# 6_-_Z7010_DDR_INF.net
KiCad netlist of a schematic drawn in Altium Designer
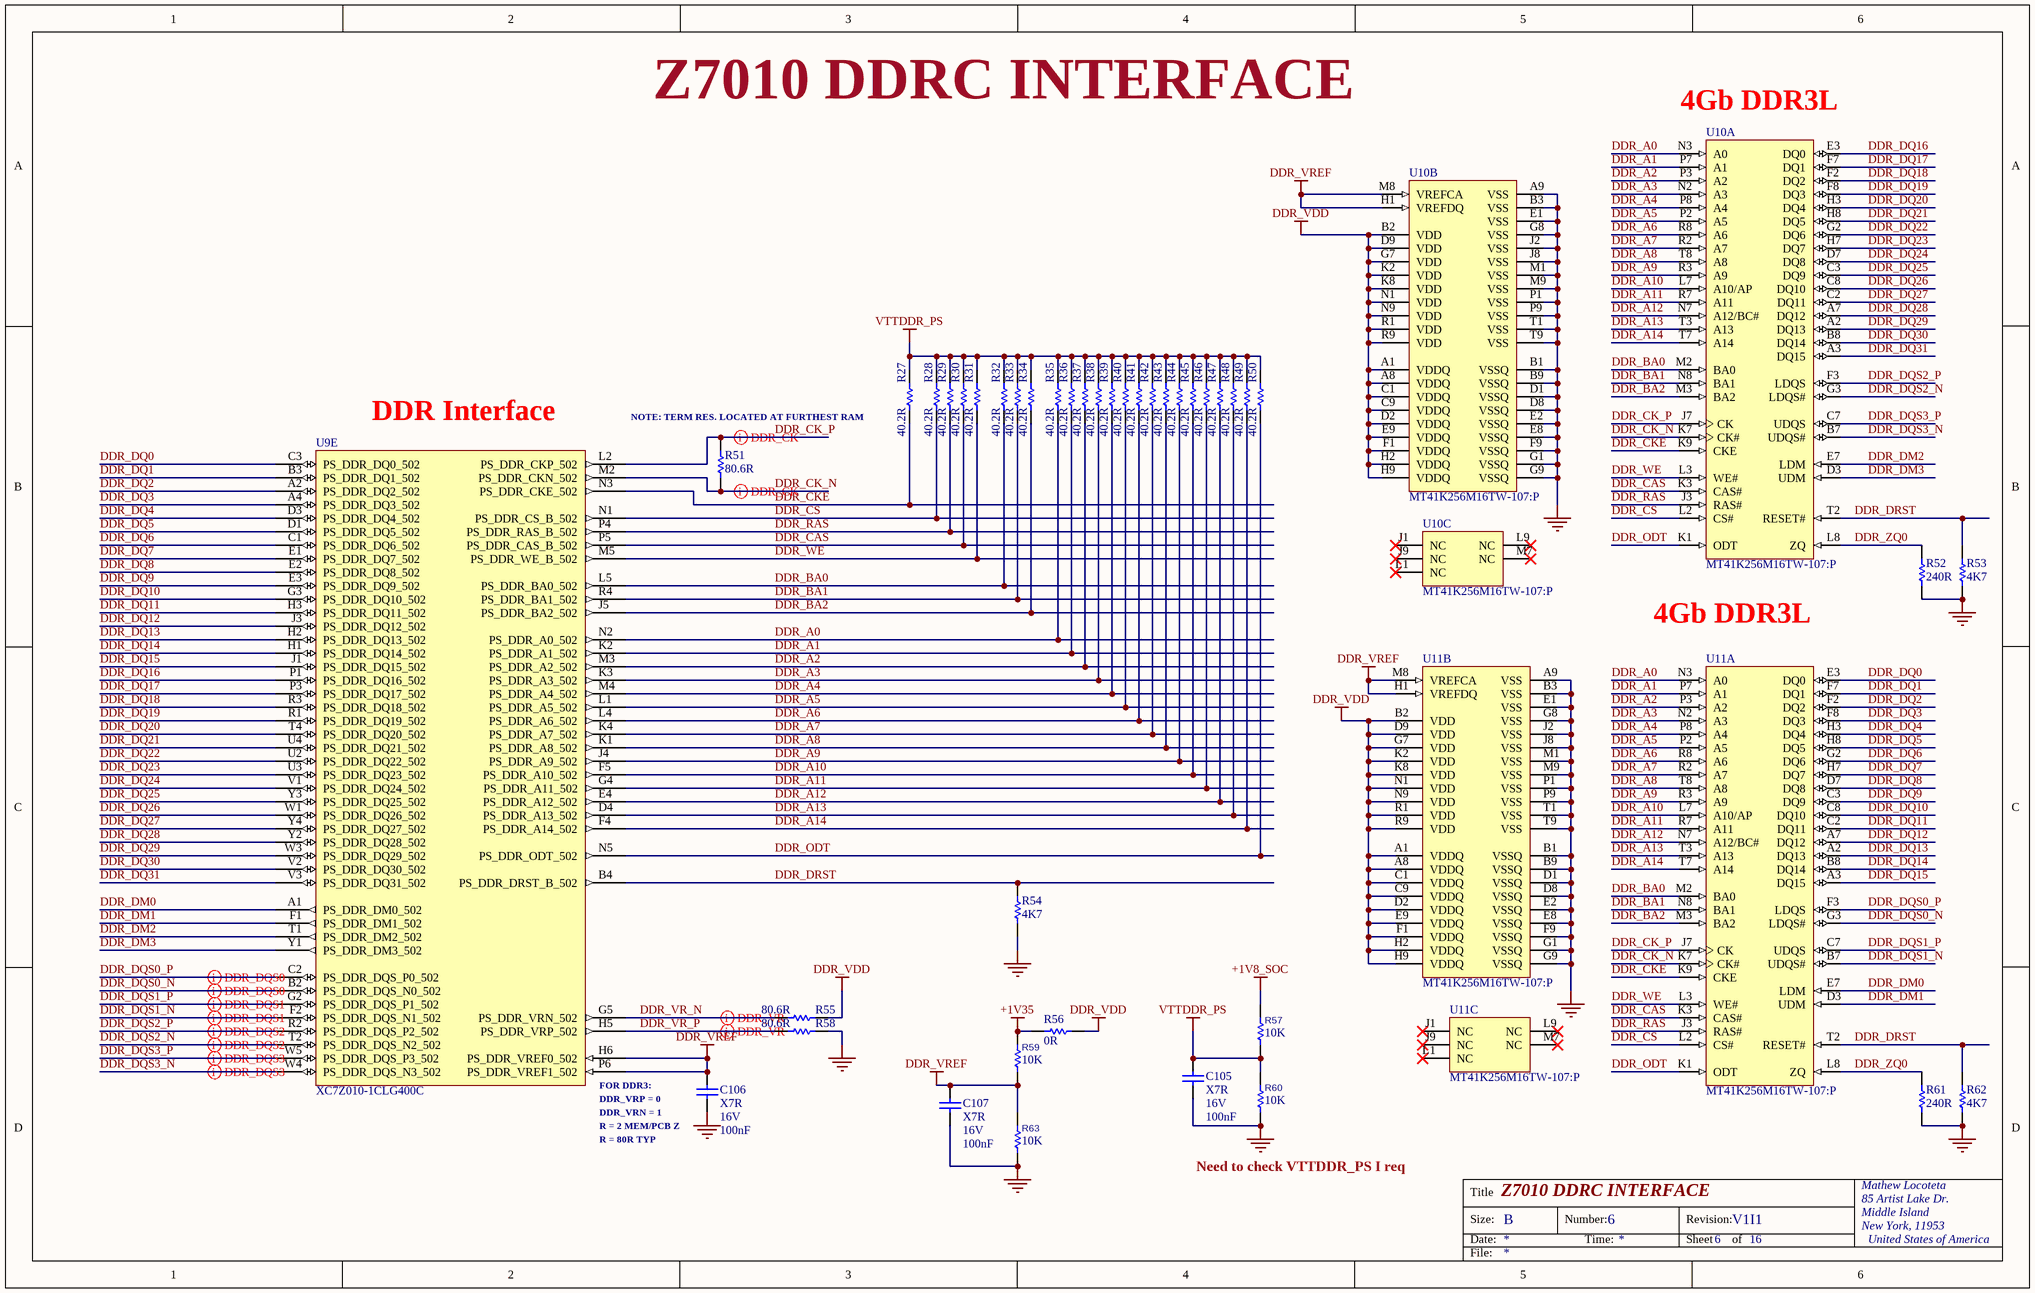
[diagram p0: [6] - Z7010 DDR INF.SchDoc]

(export (version "E")
  (design (tool "Eeschema 10.0.6"))
  (components
    (comp (ref "C105")
      (value "100nF 0402 16V")
      (fields
        (field (name "MANUFACTURER") "KEMET")
        (field (name "MANUFACTURER PART NUMBER") "C0402C104J4RACTU")
        (field (name "TOLERANCE") "5%")
        (field (name "DIELECTRIC") "X7R")
        (field (name "VOLTAGE RATING") "16V")
        (field (name "CAPACITANCE") "100nF")
      )
      (libsource (lib "Zynq 7000") (part "C0402C104J4RACTU"))
    )
    (comp (ref "C106")
      (value "100nF 0402 16V")
      (fields
        (field (name "MANUFACTURER") "KEMET")
        (field (name "MANUFACTURER PART NUMBER") "C0402C104J4RACTU")
        (field (name "TOLERANCE") "5%")
        (field (name "DIELECTRIC") "X7R")
        (field (name "VOLTAGE RATING") "16V")
        (field (name "CAPACITANCE") "100nF")
      )
      (libsource (lib "Zynq 7000") (part "C0402C104J4RACTU"))
    )
    (comp (ref "C107")
      (value "100nF 0402 16V")
      (fields
        (field (name "MANUFACTURER") "KEMET")
        (field (name "MANUFACTURER PART NUMBER") "C0402C104J4RACTU")
        (field (name "TOLERANCE") "5%")
        (field (name "DIELECTRIC") "X7R")
        (field (name "VOLTAGE RATING") "16V")
        (field (name "CAPACITANCE") "100nF")
      )
      (libsource (lib "Zynq 7000") (part "C0402C104J4RACTU"))
    )
    (comp (ref "R27")
      (value "40R2 1% 0402")
      (description "RES SMD 40.2 OHM 1% 1/16W 0402")
      (fields
        (field (name "MANUFACTURER") "Vishay")
        (field (name "MANUFACTURER PART NUMBER") "CRCW040240R2FKED")
        (field (name "RESISTANCE") "40.2R")
      )
      (libsource (lib "Zynq 7000") (part "CRCW040240R2FKED"))
    )
    (comp (ref "R28")
      (value "40R2 1% 0402")
      (description "RES SMD 40.2 OHM 1% 1/16W 0402")
      (fields
        (field (name "MANUFACTURER") "Vishay")
        (field (name "MANUFACTURER PART NUMBER") "CRCW040240R2FKED")
        (field (name "RESISTANCE") "40.2R")
      )
      (libsource (lib "Zynq 7000") (part "CRCW040240R2FKED"))
    )
    (comp (ref "R29")
      (value "40R2 1% 0402")
      (description "RES SMD 40.2 OHM 1% 1/16W 0402")
      (fields
        (field (name "MANUFACTURER") "Vishay")
        (field (name "MANUFACTURER PART NUMBER") "CRCW040240R2FKED")
        (field (name "RESISTANCE") "40.2R")
      )
      (libsource (lib "Zynq 7000") (part "CRCW040240R2FKED"))
    )
    (comp (ref "R30")
      (value "40R2 1% 0402")
      (description "RES SMD 40.2 OHM 1% 1/16W 0402")
      (fields
        (field (name "MANUFACTURER") "Vishay")
        (field (name "MANUFACTURER PART NUMBER") "CRCW040240R2FKED")
        (field (name "RESISTANCE") "40.2R")
      )
      (libsource (lib "Zynq 7000") (part "CRCW040240R2FKED"))
    )
    (comp (ref "R31")
      (value "40R2 1% 0402")
      (description "RES SMD 40.2 OHM 1% 1/16W 0402")
      (fields
        (field (name "MANUFACTURER") "Vishay")
        (field (name "MANUFACTURER PART NUMBER") "CRCW040240R2FKED")
        (field (name "RESISTANCE") "40.2R")
      )
      (libsource (lib "Zynq 7000") (part "CRCW040240R2FKED"))
    )
    (comp (ref "R32")
      (value "40R2 1% 0402")
      (description "RES SMD 40.2 OHM 1% 1/16W 0402")
      (fields
        (field (name "MANUFACTURER") "Vishay")
        (field (name "MANUFACTURER PART NUMBER") "CRCW040240R2FKED")
        (field (name "RESISTANCE") "40.2R")
      )
      (libsource (lib "Zynq 7000") (part "CRCW040240R2FKED"))
    )
    (comp (ref "R33")
      (value "40R2 1% 0402")
      (description "RES SMD 40.2 OHM 1% 1/16W 0402")
      (fields
        (field (name "MANUFACTURER") "Vishay")
        (field (name "MANUFACTURER PART NUMBER") "CRCW040240R2FKED")
        (field (name "RESISTANCE") "40.2R")
      )
      (libsource (lib "Zynq 7000") (part "CRCW040240R2FKED"))
    )
    (comp (ref "R34")
      (value "40R2 1% 0402")
      (description "RES SMD 40.2 OHM 1% 1/16W 0402")
      (fields
        (field (name "MANUFACTURER") "Vishay")
        (field (name "MANUFACTURER PART NUMBER") "CRCW040240R2FKED")
        (field (name "RESISTANCE") "40.2R")
      )
      (libsource (lib "Zynq 7000") (part "CRCW040240R2FKED"))
    )
    (comp (ref "R35")
      (value "40R2 1% 0402")
      (description "RES SMD 40.2 OHM 1% 1/16W 0402")
      (fields
        (field (name "MANUFACTURER") "Vishay")
        (field (name "MANUFACTURER PART NUMBER") "CRCW040240R2FKED")
        (field (name "RESISTANCE") "40.2R")
      )
      (libsource (lib "Zynq 7000") (part "CRCW040240R2FKED"))
    )
    (comp (ref "R36")
      (value "40R2 1% 0402")
      (description "RES SMD 40.2 OHM 1% 1/16W 0402")
      (fields
        (field (name "MANUFACTURER") "Vishay")
        (field (name "MANUFACTURER PART NUMBER") "CRCW040240R2FKED")
        (field (name "RESISTANCE") "40.2R")
      )
      (libsource (lib "Zynq 7000") (part "CRCW040240R2FKED"))
    )
    (comp (ref "R37")
      (value "40R2 1% 0402")
      (description "RES SMD 40.2 OHM 1% 1/16W 0402")
      (fields
        (field (name "MANUFACTURER") "Vishay")
        (field (name "MANUFACTURER PART NUMBER") "CRCW040240R2FKED")
        (field (name "RESISTANCE") "40.2R")
      )
      (libsource (lib "Zynq 7000") (part "CRCW040240R2FKED"))
    )
    (comp (ref "R38")
      (value "40R2 1% 0402")
      (description "RES SMD 40.2 OHM 1% 1/16W 0402")
      (fields
        (field (name "MANUFACTURER") "Vishay")
        (field (name "MANUFACTURER PART NUMBER") "CRCW040240R2FKED")
        (field (name "RESISTANCE") "40.2R")
      )
      (libsource (lib "Zynq 7000") (part "CRCW040240R2FKED"))
    )
    (comp (ref "R39")
      (value "40R2 1% 0402")
      (description "RES SMD 40.2 OHM 1% 1/16W 0402")
      (fields
        (field (name "MANUFACTURER") "Vishay")
        (field (name "MANUFACTURER PART NUMBER") "CRCW040240R2FKED")
        (field (name "RESISTANCE") "40.2R")
      )
      (libsource (lib "Zynq 7000") (part "CRCW040240R2FKED"))
    )
    (comp (ref "R40")
      (value "40R2 1% 0402")
      (description "RES SMD 40.2 OHM 1% 1/16W 0402")
      (fields
        (field (name "MANUFACTURER") "Vishay")
        (field (name "MANUFACTURER PART NUMBER") "CRCW040240R2FKED")
        (field (name "RESISTANCE") "40.2R")
      )
      (libsource (lib "Zynq 7000") (part "CRCW040240R2FKED"))
    )
    (comp (ref "R41")
      (value "40R2 1% 0402")
      (description "RES SMD 40.2 OHM 1% 1/16W 0402")
      (fields
        (field (name "MANUFACTURER") "Vishay")
        (field (name "MANUFACTURER PART NUMBER") "CRCW040240R2FKED")
        (field (name "RESISTANCE") "40.2R")
      )
      (libsource (lib "Zynq 7000") (part "CRCW040240R2FKED"))
    )
    (comp (ref "R42")
      (value "40R2 1% 0402")
      (description "RES SMD 40.2 OHM 1% 1/16W 0402")
      (fields
        (field (name "MANUFACTURER") "Vishay")
        (field (name "MANUFACTURER PART NUMBER") "CRCW040240R2FKED")
        (field (name "RESISTANCE") "40.2R")
      )
      (libsource (lib "Zynq 7000") (part "CRCW040240R2FKED"))
    )
    (comp (ref "R43")
      (value "40R2 1% 0402")
      (description "RES SMD 40.2 OHM 1% 1/16W 0402")
      (fields
        (field (name "MANUFACTURER") "Vishay")
        (field (name "MANUFACTURER PART NUMBER") "CRCW040240R2FKED")
        (field (name "RESISTANCE") "40.2R")
      )
      (libsource (lib "Zynq 7000") (part "CRCW040240R2FKED"))
    )
    (comp (ref "R44")
      (value "40R2 1% 0402")
      (description "RES SMD 40.2 OHM 1% 1/16W 0402")
      (fields
        (field (name "MANUFACTURER") "Vishay")
        (field (name "MANUFACTURER PART NUMBER") "CRCW040240R2FKED")
        (field (name "RESISTANCE") "40.2R")
      )
      (libsource (lib "Zynq 7000") (part "CRCW040240R2FKED"))
    )
    (comp (ref "R45")
      (value "40R2 1% 0402")
      (description "RES SMD 40.2 OHM 1% 1/16W 0402")
      (fields
        (field (name "MANUFACTURER") "Vishay")
        (field (name "MANUFACTURER PART NUMBER") "CRCW040240R2FKED")
        (field (name "RESISTANCE") "40.2R")
      )
      (libsource (lib "Zynq 7000") (part "CRCW040240R2FKED"))
    )
    (comp (ref "R46")
      (value "40R2 1% 0402")
      (description "RES SMD 40.2 OHM 1% 1/16W 0402")
      (fields
        (field (name "MANUFACTURER") "Vishay")
        (field (name "MANUFACTURER PART NUMBER") "CRCW040240R2FKED")
        (field (name "RESISTANCE") "40.2R")
      )
      (libsource (lib "Zynq 7000") (part "CRCW040240R2FKED"))
    )
    (comp (ref "R47")
      (value "40R2 1% 0402")
      (description "RES SMD 40.2 OHM 1% 1/16W 0402")
      (fields
        (field (name "MANUFACTURER") "Vishay")
        (field (name "MANUFACTURER PART NUMBER") "CRCW040240R2FKED")
        (field (name "RESISTANCE") "40.2R")
      )
      (libsource (lib "Zynq 7000") (part "CRCW040240R2FKED"))
    )
    (comp (ref "R48")
      (value "40R2 1% 0402")
      (description "RES SMD 40.2 OHM 1% 1/16W 0402")
      (fields
        (field (name "MANUFACTURER") "Vishay")
        (field (name "MANUFACTURER PART NUMBER") "CRCW040240R2FKED")
        (field (name "RESISTANCE") "40.2R")
      )
      (libsource (lib "Zynq 7000") (part "CRCW040240R2FKED"))
    )
    (comp (ref "R49")
      (value "40R2 1% 0402")
      (description "RES SMD 40.2 OHM 1% 1/16W 0402")
      (fields
        (field (name "MANUFACTURER") "Vishay")
        (field (name "MANUFACTURER PART NUMBER") "CRCW040240R2FKED")
        (field (name "RESISTANCE") "40.2R")
      )
      (libsource (lib "Zynq 7000") (part "CRCW040240R2FKED"))
    )
    (comp (ref "R50")
      (value "40R2 1% 0402")
      (description "RES SMD 40.2 OHM 1% 1/16W 0402")
      (fields
        (field (name "MANUFACTURER") "Vishay")
        (field (name "MANUFACTURER PART NUMBER") "CRCW040240R2FKED")
        (field (name "RESISTANCE") "40.2R")
      )
      (libsource (lib "Zynq 7000") (part "CRCW040240R2FKED"))
    )
    (comp (ref "R51")
      (value "80.6R 0402 1%")
      (fields
        (field (name "MANUFACTURER") "Vishay")
        (field (name "MANUFACTURER PART NUMBER") "CRCW040280R6FKED")
        (field (name "TOLERANCE") "1%")
        (field (name "RESISTANCE") "80.6R")
      )
      (libsource (lib "Zynq 7000") (part "CRCW040280R6FKED"))
    )
    (comp (ref "R52")
      (value "240R 0402 1%")
      (description "RES SMD 240 OHM 1% 1/16W 0402")
      (fields
        (field (name "MANUFACTURER") "Vishay")
        (field (name "MANUFACTURER PART NUMBER") "CRCW0402240RFKED")
        (field (name "RESISTANCE") "240R")
      )
      (libsource (lib "Zynq 7000") (part "CRCW0402240RFKED"))
    )
    (comp (ref "R53")
      (value "4K7 0402 1%")
      (description "Resistor SMD 4.7 kOhm 0402 PU=10000 ST, CRCW04024K70FKED, Vishay")
      (fields
        (field (name "MANUFACTURER") "Vishay")
        (field (name "MANUFACTURER PART NUMBER") "CRCW04024K70FKED")
        (field (name "RESISTANCE") "4K7")
      )
      (libsource (lib "Zynq 7000") (part "CRCW04024K70FKED"))
    )
    (comp (ref "R54")
      (value "4K7 0402 1%")
      (description "Resistor SMD 4.7 kOhm 0402 PU=10000 ST, CRCW04024K70FKED, Vishay")
      (fields
        (field (name "MANUFACTURER") "Vishay")
        (field (name "MANUFACTURER PART NUMBER") "CRCW04024K70FKED")
        (field (name "RESISTANCE") "4K7")
      )
      (libsource (lib "Zynq 7000") (part "CRCW04024K70FKED"))
    )
    (comp (ref "R55")
      (value "80.6R 0402 1%")
      (fields
        (field (name "MANUFACTURER") "Vishay")
        (field (name "MANUFACTURER PART NUMBER") "CRCW040280R6FKED")
        (field (name "TOLERANCE") "1%")
        (field (name "RESISTANCE") "80.6R")
      )
      (libsource (lib "Zynq 7000") (part "CRCW040280R6FKED"))
    )
    (comp (ref "R56")
      (value "0R")
      (footprint "r0805")
      (fields
        (field (name "MANUFACTURER") "Stackpole Electronics")
        (field (name "MANUFACTURER PART NUMBER") "RMCF0805ZT0R00")
      )
      (libsource (lib "DVXC4+ ECU (2)") (part "RMCF0805ZT0R00"))
    )
    (comp (ref "R57")
      (value "10K")
      (footprint "R0402")
      (description "RES 10K OHM 1% 1/16W 0402")
      (fields
        (field (name "MANUFACTURER") "Stackpole Electronics")
        (field (name "MANUFACTURER PART NUMBER") "RMCF0402FT10K0")
      )
      (libsource (lib "DVXC4+ ECU (2)") (part "RMCF0402FT10K0"))
    )
    (comp (ref "R58")
      (value "80.6R 0402 1%")
      (fields
        (field (name "MANUFACTURER") "Vishay")
        (field (name "MANUFACTURER PART NUMBER") "CRCW040280R6FKED")
        (field (name "TOLERANCE") "1%")
        (field (name "RESISTANCE") "80.6R")
      )
      (libsource (lib "Zynq 7000") (part "CRCW040280R6FKED"))
    )
    (comp (ref "R59")
      (value "10K")
      (footprint "R0402")
      (description "RES 10K OHM 1% 1/16W 0402")
      (fields
        (field (name "MANUFACTURER") "Stackpole Electronics")
        (field (name "MANUFACTURER PART NUMBER") "RMCF0402FT10K0")
      )
      (libsource (lib "DVXC4+ ECU (2)") (part "RMCF0402FT10K0"))
    )
    (comp (ref "R60")
      (value "10K")
      (footprint "R0402")
      (description "RES 10K OHM 1% 1/16W 0402")
      (fields
        (field (name "MANUFACTURER") "Stackpole Electronics")
        (field (name "MANUFACTURER PART NUMBER") "RMCF0402FT10K0")
      )
      (libsource (lib "DVXC4+ ECU (2)") (part "RMCF0402FT10K0"))
    )
    (comp (ref "R61")
      (value "240R 0402 1%")
      (description "RES SMD 240 OHM 1% 1/16W 0402")
      (fields
        (field (name "MANUFACTURER") "Vishay")
        (field (name "MANUFACTURER PART NUMBER") "CRCW0402240RFKED")
        (field (name "RESISTANCE") "240R")
      )
      (libsource (lib "Zynq 7000") (part "CRCW0402240RFKED"))
    )
    (comp (ref "R62")
      (value "4K7 0402 1%")
      (description "Resistor SMD 4.7 kOhm 0402 PU=10000 ST, CRCW04024K70FKED, Vishay")
      (fields
        (field (name "MANUFACTURER") "Vishay")
        (field (name "MANUFACTURER PART NUMBER") "CRCW04024K70FKED")
        (field (name "RESISTANCE") "4K7")
      )
      (libsource (lib "Zynq 7000") (part "CRCW04024K70FKED"))
    )
    (comp (ref "R63")
      (value "10K")
      (footprint "R0402")
      (description "RES 10K OHM 1% 1/16W 0402")
      (fields
        (field (name "MANUFACTURER") "Stackpole Electronics")
        (field (name "MANUFACTURER PART NUMBER") "RMCF0402FT10K0")
      )
      (libsource (lib "DVXC4+ ECU (2)") (part "RMCF0402FT10K0"))
    )
    (comp (ref "U9")
      (value "XC7Z010-1CLG400C")
      (footprint "CLG400")
      (fields (field (name "GENERIC PART NUMBER") "XC7Z010"))
      (libsource (lib "Altium Content Vault") (part "XNLX-XC7Z010-CLG400"))
    )
    (comp (ref "U10")
      (value "MT41K256M16TW-107:P")
      (footprint "MICT-TW-96")
      (description "DDR3L SDRAM, 4 GB, 933 MHz, 1.283 to 1.45 V, 0 to 95 degC, 96-Pin FBGA, RoHS, Tray")
      (fields (field (name "MANUFACTURER") "Micron"))
      (libsource (lib "Altium Content Vault") (part "MICT-MT41K256M16-TW-96"))
    )
    (comp (ref "U11")
      (value "MT41K256M16TW-107:P")
      (footprint "MICT-TW-96")
      (description "DDR3L SDRAM, 4 GB, 933 MHz, 1.283 to 1.45 V, 0 to 95 degC, 96-Pin FBGA, RoHS, Tray")
      (fields (field (name "MANUFACTURER") "Micron"))
      (libsource (lib "Altium Content Vault") (part "MICT-MT41K256M16-TW-96"))
    )
  )
  (nets
    (net (code "1") (name "+1V8_SOC") (class "Default")
      (node (ref "R57") (pin "2") (pinfunction "2_2") (pintype "passive"))
    )
    (net (code "2") (name "+1V35") (class "Default")
      (node (ref "R56") (pin "2") (pinfunction "2_2") (pintype "passive"))
      (node (ref "R59") (pin "2") (pinfunction "2_2") (pintype "passive"))
    )
    (net (code "3") (name "/DDR_A0") (class "Default")
      (node (ref "R35") (pin "1") (pinfunction "1_1") (pintype "passive"))
      (node (ref "U10") (pin "N3") (pinfunction "A0_N3") (pintype "input"))
      (node (ref "U11") (pin "N3") (pinfunction "A0_N3") (pintype "input"))
      (node (ref "U9") (pin "N2") (pinfunction "PS_DDR_A0_502_N2") (pintype "output"))
    )
    (net (code "4") (name "/DDR_A1") (class "Default")
      (node (ref "R36") (pin "1") (pinfunction "1_1") (pintype "passive"))
      (node (ref "U10") (pin "P7") (pinfunction "A1_P7") (pintype "input"))
      (node (ref "U11") (pin "P7") (pinfunction "A1_P7") (pintype "input"))
      (node (ref "U9") (pin "K2") (pinfunction "PS_DDR_A1_502_K2") (pintype "output"))
    )
    (net (code "5") (name "/DDR_A2") (class "Default")
      (node (ref "R37") (pin "1") (pinfunction "1_1") (pintype "passive"))
      (node (ref "U10") (pin "P3") (pinfunction "A2_P3") (pintype "input"))
      (node (ref "U11") (pin "P3") (pinfunction "A2_P3") (pintype "input"))
      (node (ref "U9") (pin "M3") (pinfunction "PS_DDR_A2_502_M3") (pintype "output"))
    )
    (net (code "6") (name "/DDR_A3") (class "Default")
      (node (ref "R38") (pin "1") (pinfunction "1_1") (pintype "passive"))
      (node (ref "U10") (pin "N2") (pinfunction "A3_N2") (pintype "input"))
      (node (ref "U11") (pin "N2") (pinfunction "A3_N2") (pintype "input"))
      (node (ref "U9") (pin "K3") (pinfunction "PS_DDR_A3_502_K3") (pintype "output"))
    )
    (net (code "7") (name "/DDR_A4") (class "Default")
      (node (ref "R39") (pin "1") (pinfunction "1_1") (pintype "passive"))
      (node (ref "U10") (pin "P8") (pinfunction "A4_P8") (pintype "input"))
      (node (ref "U11") (pin "P8") (pinfunction "A4_P8") (pintype "input"))
      (node (ref "U9") (pin "M4") (pinfunction "PS_DDR_A4_502_M4") (pintype "output"))
    )
    (net (code "8") (name "/DDR_A5") (class "Default")
      (node (ref "R40") (pin "1") (pinfunction "1_1") (pintype "passive"))
      (node (ref "U10") (pin "P2") (pinfunction "A5_P2") (pintype "input"))
      (node (ref "U11") (pin "P2") (pinfunction "A5_P2") (pintype "input"))
      (node (ref "U9") (pin "L1") (pinfunction "PS_DDR_A5_502_L1") (pintype "output"))
    )
    (net (code "9") (name "/DDR_A6") (class "Default")
      (node (ref "R41") (pin "1") (pinfunction "1_1") (pintype "passive"))
      (node (ref "U10") (pin "R8") (pinfunction "A6_R8") (pintype "input"))
      (node (ref "U11") (pin "R8") (pinfunction "A6_R8") (pintype "input"))
      (node (ref "U9") (pin "L4") (pinfunction "PS_DDR_A6_502_L4") (pintype "output"))
    )
    (net (code "10") (name "/DDR_A7") (class "Default")
      (node (ref "R42") (pin "1") (pinfunction "1_1") (pintype "passive"))
      (node (ref "U10") (pin "R2") (pinfunction "A7_R2") (pintype "input"))
      (node (ref "U11") (pin "R2") (pinfunction "A7_R2") (pintype "input"))
      (node (ref "U9") (pin "K4") (pinfunction "PS_DDR_A7_502_K4") (pintype "output"))
    )
    (net (code "11") (name "/DDR_A8") (class "Default")
      (node (ref "R43") (pin "1") (pinfunction "1_1") (pintype "passive"))
      (node (ref "U10") (pin "T8") (pinfunction "A8_T8") (pintype "input"))
      (node (ref "U11") (pin "T8") (pinfunction "A8_T8") (pintype "input"))
      (node (ref "U9") (pin "K1") (pinfunction "PS_DDR_A8_502_K1") (pintype "output"))
    )
    (net (code "12") (name "/DDR_A9") (class "Default")
      (node (ref "R44") (pin "1") (pinfunction "1_1") (pintype "passive"))
      (node (ref "U10") (pin "R3") (pinfunction "A9_R3") (pintype "input"))
      (node (ref "U11") (pin "R3") (pinfunction "A9_R3") (pintype "input"))
      (node (ref "U9") (pin "J4") (pinfunction "PS_DDR_A9_502_J4") (pintype "output"))
    )
    (net (code "13") (name "/DDR_A10") (class "Default")
      (node (ref "R45") (pin "1") (pinfunction "1_1") (pintype "passive"))
      (node (ref "U10") (pin "L7") (pinfunction "A10/AP_L7") (pintype "input"))
      (node (ref "U11") (pin "L7") (pinfunction "A10/AP_L7") (pintype "input"))
      (node (ref "U9") (pin "F5") (pinfunction "PS_DDR_A10_502_F5") (pintype "output"))
    )
    (net (code "14") (name "/DDR_A11") (class "Default")
      (node (ref "R46") (pin "1") (pinfunction "1_1") (pintype "passive"))
      (node (ref "U10") (pin "R7") (pinfunction "A11_R7") (pintype "input"))
      (node (ref "U11") (pin "R7") (pinfunction "A11_R7") (pintype "input"))
      (node (ref "U9") (pin "G4") (pinfunction "PS_DDR_A11_502_G4") (pintype "output"))
    )
    (net (code "15") (name "/DDR_A12") (class "Default")
      (node (ref "R47") (pin "1") (pinfunction "1_1") (pintype "passive"))
      (node (ref "U10") (pin "N7") (pinfunction "A12/BC#_N7") (pintype "input"))
      (node (ref "U11") (pin "N7") (pinfunction "A12/BC#_N7") (pintype "input"))
      (node (ref "U9") (pin "E4") (pinfunction "PS_DDR_A12_502_E4") (pintype "output"))
    )
    (net (code "16") (name "/DDR_A13") (class "Default")
      (node (ref "R48") (pin "1") (pinfunction "1_1") (pintype "passive"))
      (node (ref "U10") (pin "T3") (pinfunction "A13_T3") (pintype "input"))
      (node (ref "U11") (pin "T3") (pinfunction "A13_T3") (pintype "input"))
      (node (ref "U9") (pin "D4") (pinfunction "PS_DDR_A13_502_D4") (pintype "output"))
    )
    (net (code "17") (name "/DDR_A14") (class "Default")
      (node (ref "R49") (pin "1") (pinfunction "1_1") (pintype "passive"))
      (node (ref "U10") (pin "T7") (pinfunction "A14_T7") (pintype "input"))
      (node (ref "U11") (pin "T7") (pinfunction "A14_T7") (pintype "input"))
      (node (ref "U9") (pin "F4") (pinfunction "PS_DDR_A14_502_F4") (pintype "output"))
    )
    (net (code "18") (name "/DDR_BA0") (class "Default")
      (node (ref "R32") (pin "1") (pinfunction "1_1") (pintype "passive"))
      (node (ref "U10") (pin "M2") (pinfunction "BA0_M2") (pintype "input"))
      (node (ref "U11") (pin "M2") (pinfunction "BA0_M2") (pintype "input"))
      (node (ref "U9") (pin "L5") (pinfunction "PS_DDR_BA0_502_L5") (pintype "output"))
    )
    (net (code "19") (name "/DDR_BA1") (class "Default")
      (node (ref "R33") (pin "1") (pinfunction "1_1") (pintype "passive"))
      (node (ref "U10") (pin "N8") (pinfunction "BA1_N8") (pintype "input"))
      (node (ref "U11") (pin "N8") (pinfunction "BA1_N8") (pintype "input"))
      (node (ref "U9") (pin "R4") (pinfunction "PS_DDR_BA1_502_R4") (pintype "output"))
    )
    (net (code "20") (name "/DDR_BA2") (class "Default")
      (node (ref "R34") (pin "1") (pinfunction "1_1") (pintype "passive"))
      (node (ref "U10") (pin "M3") (pinfunction "BA2_M3") (pintype "input"))
      (node (ref "U11") (pin "M3") (pinfunction "BA2_M3") (pintype "input"))
      (node (ref "U9") (pin "J5") (pinfunction "PS_DDR_BA2_502_J5") (pintype "output"))
    )
    (net (code "21") (name "/DDR_CAS") (class "Default")
      (node (ref "R30") (pin "1") (pinfunction "1_1") (pintype "passive"))
      (node (ref "U10") (pin "K3") (pinfunction "CAS#_K3") (pintype "input"))
      (node (ref "U11") (pin "K3") (pinfunction "CAS#_K3") (pintype "input"))
      (node (ref "U9") (pin "P5") (pinfunction "PS_DDR_CAS_B_502_P5") (pintype "output"))
    )
    (net (code "22") (name "/DDR_CKE") (class "Default")
      (node (ref "R27") (pin "1") (pinfunction "1_1") (pintype "passive"))
      (node (ref "U10") (pin "K9") (pinfunction "CKE_K9") (pintype "input"))
      (node (ref "U11") (pin "K9") (pinfunction "CKE_K9") (pintype "input"))
      (node (ref "U9") (pin "N3") (pinfunction "PS_DDR_CKE_502_N3") (pintype "output"))
    )
    (net (code "23") (name "/DDR_CK_N") (class "Default")
      (node (ref "R51") (pin "1") (pinfunction "1_1") (pintype "passive"))
      (node (ref "U10") (pin "K7") (pinfunction "CK#_K7") (pintype "input"))
      (node (ref "U11") (pin "K7") (pinfunction "CK#_K7") (pintype "input"))
      (node (ref "U9") (pin "M2") (pinfunction "PS_DDR_CKN_502_M2") (pintype "output"))
    )
    (net (code "24") (name "/DDR_CK_P") (class "Default")
      (node (ref "R51") (pin "2") (pinfunction "2_2") (pintype "passive"))
      (node (ref "U10") (pin "J7") (pinfunction "CK_J7") (pintype "input"))
      (node (ref "U11") (pin "J7") (pinfunction "CK_J7") (pintype "input"))
      (node (ref "U9") (pin "L2") (pinfunction "PS_DDR_CKP_502_L2") (pintype "output"))
    )
    (net (code "25") (name "/DDR_CS") (class "Default")
      (node (ref "R28") (pin "1") (pinfunction "1_1") (pintype "passive"))
      (node (ref "U10") (pin "L2") (pinfunction "CS#_L2") (pintype "input"))
      (node (ref "U11") (pin "L2") (pinfunction "CS#_L2") (pintype "input"))
      (node (ref "U9") (pin "N1") (pinfunction "PS_DDR_CS_B_502_N1") (pintype "output"))
    )
    (net (code "26") (name "/DDR_DM0") (class "Default")
      (node (ref "U11") (pin "E7") (pinfunction "LDM_E7") (pintype "input"))
      (node (ref "U9") (pin "A1") (pinfunction "PS_DDR_DM0_502_A1") (pintype "output"))
    )
    (net (code "27") (name "/DDR_DM1") (class "Default")
      (node (ref "U11") (pin "D3") (pinfunction "UDM_D3") (pintype "input"))
      (node (ref "U9") (pin "F1") (pinfunction "PS_DDR_DM1_502_F1") (pintype "output"))
    )
    (net (code "28") (name "/DDR_DM2") (class "Default")
      (node (ref "U10") (pin "E7") (pinfunction "LDM_E7") (pintype "input"))
      (node (ref "U9") (pin "T1") (pinfunction "PS_DDR_DM2_502_T1") (pintype "output"))
    )
    (net (code "29") (name "/DDR_DM3") (class "Default")
      (node (ref "U10") (pin "D3") (pinfunction "UDM_D3") (pintype "input"))
      (node (ref "U9") (pin "Y1") (pinfunction "PS_DDR_DM3_502_Y1") (pintype "output"))
    )
    (net (code "30") (name "/DDR_DQ0") (class "Default")
      (node (ref "U11") (pin "E3") (pinfunction "DQ0_E3") (pintype "bidirectional"))
      (node (ref "U9") (pin "C3") (pinfunction "PS_DDR_DQ0_502_C3") (pintype "bidirectional"))
    )
    (net (code "31") (name "/DDR_DQ1") (class "Default")
      (node (ref "U11") (pin "F7") (pinfunction "DQ1_F7") (pintype "bidirectional"))
      (node (ref "U9") (pin "B3") (pinfunction "PS_DDR_DQ1_502_B3") (pintype "bidirectional"))
    )
    (net (code "32") (name "/DDR_DQ2") (class "Default")
      (node (ref "U11") (pin "F2") (pinfunction "DQ2_F2") (pintype "bidirectional"))
      (node (ref "U9") (pin "A2") (pinfunction "PS_DDR_DQ2_502_A2") (pintype "bidirectional"))
    )
    (net (code "33") (name "/DDR_DQ3") (class "Default")
      (node (ref "U11") (pin "F8") (pinfunction "DQ3_F8") (pintype "bidirectional"))
      (node (ref "U9") (pin "A4") (pinfunction "PS_DDR_DQ3_502_A4") (pintype "bidirectional"))
    )
    (net (code "34") (name "/DDR_DQ4") (class "Default")
      (node (ref "U11") (pin "H3") (pinfunction "DQ4_H3") (pintype "bidirectional"))
      (node (ref "U9") (pin "D3") (pinfunction "PS_DDR_DQ4_502_D3") (pintype "bidirectional"))
    )
    (net (code "35") (name "/DDR_DQ5") (class "Default")
      (node (ref "U11") (pin "H8") (pinfunction "DQ5_H8") (pintype "bidirectional"))
      (node (ref "U9") (pin "D1") (pinfunction "PS_DDR_DQ5_502_D1") (pintype "bidirectional"))
    )
    (net (code "36") (name "/DDR_DQ6") (class "Default")
      (node (ref "U11") (pin "G2") (pinfunction "DQ6_G2") (pintype "bidirectional"))
      (node (ref "U9") (pin "C1") (pinfunction "PS_DDR_DQ6_502_C1") (pintype "bidirectional"))
    )
    (net (code "37") (name "/DDR_DQ7") (class "Default")
      (node (ref "U11") (pin "H7") (pinfunction "DQ7_H7") (pintype "bidirectional"))
      (node (ref "U9") (pin "E1") (pinfunction "PS_DDR_DQ7_502_E1") (pintype "bidirectional"))
    )
    (net (code "38") (name "/DDR_DQ8") (class "Default")
      (node (ref "U11") (pin "D7") (pinfunction "DQ8_D7") (pintype "bidirectional"))
      (node (ref "U9") (pin "E2") (pinfunction "PS_DDR_DQ8_502_E2") (pintype "bidirectional"))
    )
    (net (code "39") (name "/DDR_DQ9") (class "Default")
      (node (ref "U11") (pin "C3") (pinfunction "DQ9_C3") (pintype "bidirectional"))
      (node (ref "U9") (pin "E3") (pinfunction "PS_DDR_DQ9_502_E3") (pintype "bidirectional"))
    )
    (net (code "40") (name "/DDR_DQ10") (class "Default")
      (node (ref "U11") (pin "C8") (pinfunction "DQ10_C8") (pintype "bidirectional"))
      (node (ref "U9") (pin "G3") (pinfunction "PS_DDR_DQ10_502_G3") (pintype "bidirectional"))
    )
    (net (code "41") (name "/DDR_DQ11") (class "Default")
      (node (ref "U11") (pin "C2") (pinfunction "DQ11_C2") (pintype "bidirectional"))
      (node (ref "U9") (pin "H3") (pinfunction "PS_DDR_DQ11_502_H3") (pintype "bidirectional"))
    )
    (net (code "42") (name "/DDR_DQ12") (class "Default")
      (node (ref "U11") (pin "A7") (pinfunction "DQ12_A7") (pintype "bidirectional"))
      (node (ref "U9") (pin "J3") (pinfunction "PS_DDR_DQ12_502_J3") (pintype "bidirectional"))
    )
    (net (code "43") (name "/DDR_DQ13") (class "Default")
      (node (ref "U11") (pin "A2") (pinfunction "DQ13_A2") (pintype "bidirectional"))
      (node (ref "U9") (pin "H2") (pinfunction "PS_DDR_DQ13_502_H2") (pintype "bidirectional"))
    )
    (net (code "44") (name "/DDR_DQ14") (class "Default")
      (node (ref "U11") (pin "B8") (pinfunction "DQ14_B8") (pintype "bidirectional"))
      (node (ref "U9") (pin "H1") (pinfunction "PS_DDR_DQ14_502_H1") (pintype "bidirectional"))
    )
    (net (code "45") (name "/DDR_DQ15") (class "Default")
      (node (ref "U11") (pin "A3") (pinfunction "DQ15_A3") (pintype "bidirectional"))
      (node (ref "U9") (pin "J1") (pinfunction "PS_DDR_DQ15_502_J1") (pintype "bidirectional"))
    )
    (net (code "46") (name "/DDR_DQ16") (class "Default")
      (node (ref "U10") (pin "E3") (pinfunction "DQ0_E3") (pintype "bidirectional"))
      (node (ref "U9") (pin "P1") (pinfunction "PS_DDR_DQ16_502_P1") (pintype "bidirectional"))
    )
    (net (code "47") (name "/DDR_DQ17") (class "Default")
      (node (ref "U10") (pin "F7") (pinfunction "DQ1_F7") (pintype "bidirectional"))
      (node (ref "U9") (pin "P3") (pinfunction "PS_DDR_DQ17_502_P3") (pintype "bidirectional"))
    )
    (net (code "48") (name "/DDR_DQ18") (class "Default")
      (node (ref "U10") (pin "F2") (pinfunction "DQ2_F2") (pintype "bidirectional"))
      (node (ref "U9") (pin "R3") (pinfunction "PS_DDR_DQ18_502_R3") (pintype "bidirectional"))
    )
    (net (code "49") (name "/DDR_DQ19") (class "Default")
      (node (ref "U10") (pin "F8") (pinfunction "DQ3_F8") (pintype "bidirectional"))
      (node (ref "U9") (pin "R1") (pinfunction "PS_DDR_DQ19_502_R1") (pintype "bidirectional"))
    )
    (net (code "50") (name "/DDR_DQ20") (class "Default")
      (node (ref "U10") (pin "H3") (pinfunction "DQ4_H3") (pintype "bidirectional"))
      (node (ref "U9") (pin "T4") (pinfunction "PS_DDR_DQ20_502_T4") (pintype "bidirectional"))
    )
    (net (code "51") (name "/DDR_DQ21") (class "Default")
      (node (ref "U10") (pin "H8") (pinfunction "DQ5_H8") (pintype "bidirectional"))
      (node (ref "U9") (pin "U4") (pinfunction "PS_DDR_DQ21_502_U4") (pintype "bidirectional"))
    )
    (net (code "52") (name "/DDR_DQ22") (class "Default")
      (node (ref "U10") (pin "G2") (pinfunction "DQ6_G2") (pintype "bidirectional"))
      (node (ref "U9") (pin "U2") (pinfunction "PS_DDR_DQ22_502_U2") (pintype "bidirectional"))
    )
    (net (code "53") (name "/DDR_DQ23") (class "Default")
      (node (ref "U10") (pin "H7") (pinfunction "DQ7_H7") (pintype "bidirectional"))
      (node (ref "U9") (pin "U3") (pinfunction "PS_DDR_DQ23_502_U3") (pintype "bidirectional"))
    )
    (net (code "54") (name "/DDR_DQ24") (class "Default")
      (node (ref "U10") (pin "D7") (pinfunction "DQ8_D7") (pintype "bidirectional"))
      (node (ref "U9") (pin "V1") (pinfunction "PS_DDR_DQ24_502_V1") (pintype "bidirectional"))
    )
    (net (code "55") (name "/DDR_DQ25") (class "Default")
      (node (ref "U10") (pin "C3") (pinfunction "DQ9_C3") (pintype "bidirectional"))
      (node (ref "U9") (pin "Y3") (pinfunction "PS_DDR_DQ25_502_Y3") (pintype "bidirectional"))
    )
    (net (code "56") (name "/DDR_DQ26") (class "Default")
      (node (ref "U10") (pin "C8") (pinfunction "DQ10_C8") (pintype "bidirectional"))
      (node (ref "U9") (pin "W1") (pinfunction "PS_DDR_DQ26_502_W1") (pintype "bidirectional"))
    )
    (net (code "57") (name "/DDR_DQ27") (class "Default")
      (node (ref "U10") (pin "C2") (pinfunction "DQ11_C2") (pintype "bidirectional"))
      (node (ref "U9") (pin "Y4") (pinfunction "PS_DDR_DQ27_502_Y4") (pintype "bidirectional"))
    )
    (net (code "58") (name "/DDR_DQ28") (class "Default")
      (node (ref "U10") (pin "A7") (pinfunction "DQ12_A7") (pintype "bidirectional"))
      (node (ref "U9") (pin "Y2") (pinfunction "PS_DDR_DQ28_502_Y2") (pintype "bidirectional"))
    )
    (net (code "59") (name "/DDR_DQ29") (class "Default")
      (node (ref "U10") (pin "A2") (pinfunction "DQ13_A2") (pintype "bidirectional"))
      (node (ref "U9") (pin "W3") (pinfunction "PS_DDR_DQ29_502_W3") (pintype "bidirectional"))
    )
    (net (code "60") (name "/DDR_DQ30") (class "Default")
      (node (ref "U10") (pin "B8") (pinfunction "DQ14_B8") (pintype "bidirectional"))
      (node (ref "U9") (pin "V2") (pinfunction "PS_DDR_DQ30_502_V2") (pintype "bidirectional"))
    )
    (net (code "61") (name "/DDR_DQ31") (class "Default")
      (node (ref "U10") (pin "A3") (pinfunction "DQ15_A3") (pintype "bidirectional"))
      (node (ref "U9") (pin "V3") (pinfunction "PS_DDR_DQ31_502_V3") (pintype "bidirectional"))
    )
    (net (code "62") (name "/DDR_DQS0_N") (class "Default")
      (node (ref "U11") (pin "G3") (pinfunction "LDQS#_G3") (pintype "bidirectional"))
      (node (ref "U9") (pin "B2") (pinfunction "PS_DDR_DQS_N0_502_B2") (pintype "bidirectional"))
    )
    (net (code "63") (name "/DDR_DQS0_P") (class "Default")
      (node (ref "U11") (pin "F3") (pinfunction "LDQS_F3") (pintype "bidirectional"))
      (node (ref "U9") (pin "C2") (pinfunction "PS_DDR_DQS_P0_502_C2") (pintype "bidirectional"))
    )
    (net (code "64") (name "/DDR_DQS1_N") (class "Default")
      (node (ref "U11") (pin "B7") (pinfunction "UDQS#_B7") (pintype "bidirectional"))
      (node (ref "U9") (pin "F2") (pinfunction "PS_DDR_DQS_N1_502_F2") (pintype "bidirectional"))
    )
    (net (code "65") (name "/DDR_DQS1_P") (class "Default")
      (node (ref "U11") (pin "C7") (pinfunction "UDQS_C7") (pintype "bidirectional"))
      (node (ref "U9") (pin "G2") (pinfunction "PS_DDR_DQS_P1_502_G2") (pintype "bidirectional"))
    )
    (net (code "66") (name "/DDR_DQS2_N") (class "Default")
      (node (ref "U10") (pin "G3") (pinfunction "LDQS#_G3") (pintype "bidirectional"))
      (node (ref "U9") (pin "T2") (pinfunction "PS_DDR_DQS_N2_502_T2") (pintype "bidirectional"))
    )
    (net (code "67") (name "/DDR_DQS2_P") (class "Default")
      (node (ref "U10") (pin "F3") (pinfunction "LDQS_F3") (pintype "bidirectional"))
      (node (ref "U9") (pin "R2") (pinfunction "PS_DDR_DQS_P2_502_R2") (pintype "bidirectional"))
    )
    (net (code "68") (name "/DDR_DQS3_N") (class "Default")
      (node (ref "U10") (pin "B7") (pinfunction "UDQS#_B7") (pintype "bidirectional"))
      (node (ref "U9") (pin "W4") (pinfunction "PS_DDR_DQS_N3_502_W4") (pintype "bidirectional"))
    )
    (net (code "69") (name "/DDR_DQS3_P") (class "Default")
      (node (ref "U10") (pin "C7") (pinfunction "UDQS_C7") (pintype "bidirectional"))
      (node (ref "U9") (pin "W5") (pinfunction "PS_DDR_DQS_P3_502_W5") (pintype "bidirectional"))
    )
    (net (code "70") (name "/DDR_DRST") (class "Default")
      (node (ref "R53") (pin "2") (pinfunction "2_2") (pintype "passive"))
      (node (ref "R54") (pin "2") (pinfunction "2_2") (pintype "passive"))
      (node (ref "R62") (pin "2") (pinfunction "2_2") (pintype "passive"))
      (node (ref "U10") (pin "T2") (pinfunction "RESET#_T2") (pintype "input"))
      (node (ref "U11") (pin "T2") (pinfunction "RESET#_T2") (pintype "input"))
      (node (ref "U9") (pin "B4") (pinfunction "PS_DDR_DRST_B_502_B4") (pintype "output"))
    )
    (net (code "71") (name "/DDR_ODT") (class "Default")
      (node (ref "R50") (pin "1") (pinfunction "1_1") (pintype "passive"))
      (node (ref "U10") (pin "K1") (pinfunction "ODT_K1") (pintype "input"))
      (node (ref "U11") (pin "K1") (pinfunction "ODT_K1") (pintype "input"))
      (node (ref "U9") (pin "N5") (pinfunction "PS_DDR_ODT_502_N5") (pintype "output"))
    )
    (net (code "72") (name "/DDR_RAS") (class "Default")
      (node (ref "R29") (pin "1") (pinfunction "1_1") (pintype "passive"))
      (node (ref "U10") (pin "J3") (pinfunction "RAS#_J3") (pintype "input"))
      (node (ref "U11") (pin "J3") (pinfunction "RAS#_J3") (pintype "input"))
      (node (ref "U9") (pin "P4") (pinfunction "PS_DDR_RAS_B_502_P4") (pintype "output"))
    )
    (net (code "73") (name "/DDR_VR_N") (class "Default")
      (node (ref "R55") (pin "1") (pinfunction "1_1") (pintype "passive"))
      (node (ref "U9") (pin "G5") (pinfunction "PS_DDR_VRN_502_G5") (pintype "output"))
    )
    (net (code "74") (name "/DDR_VR_P") (class "Default")
      (node (ref "R58") (pin "1") (pinfunction "1_1") (pintype "passive"))
      (node (ref "U9") (pin "H5") (pinfunction "PS_DDR_VRP_502_H5") (pintype "output"))
    )
    (net (code "75") (name "/DDR_WE") (class "Default")
      (node (ref "R31") (pin "1") (pinfunction "1_1") (pintype "passive"))
      (node (ref "U10") (pin "L3") (pinfunction "WE#_L3") (pintype "input"))
      (node (ref "U11") (pin "L3") (pinfunction "WE#_L3") (pintype "input"))
      (node (ref "U9") (pin "M5") (pinfunction "PS_DDR_WE_B_502_M5") (pintype "output"))
    )
    (net (code "76") (name "/DDR_ZQ0") (class "Default")
      (node (ref "R52") (pin "2") (pinfunction "2_2") (pintype "passive"))
      (node (ref "R61") (pin "2") (pinfunction "2_2") (pintype "passive"))
      (node (ref "U10") (pin "L8") (pinfunction "ZQ_L8") (pintype "input"))
      (node (ref "U11") (pin "L8") (pinfunction "ZQ_L8") (pintype "input"))
    )
    (net (code "77") (name "DDR_VDD") (class "Default")
      (node (ref "R55") (pin "2") (pinfunction "2_2") (pintype "passive"))
      (node (ref "R56") (pin "1") (pinfunction "1_1") (pintype "passive"))
      (node (ref "U10") (pin "A1") (pinfunction "VDDQ_A1") (pintype "power_in"))
      (node (ref "U10") (pin "A8") (pinfunction "VDDQ_A8") (pintype "power_in"))
      (node (ref "U10") (pin "B2") (pinfunction "VDD_B2") (pintype "power_in"))
      (node (ref "U10") (pin "C1") (pinfunction "VDDQ_C1") (pintype "power_in"))
      (node (ref "U10") (pin "C9") (pinfunction "VDDQ_C9") (pintype "power_in"))
      (node (ref "U10") (pin "D2") (pinfunction "VDDQ_D2") (pintype "power_in"))
      (node (ref "U10") (pin "D9") (pinfunction "VDD_D9") (pintype "power_in"))
      (node (ref "U10") (pin "E9") (pinfunction "VDDQ_E9") (pintype "power_in"))
      (node (ref "U10") (pin "F1") (pinfunction "VDDQ_F1") (pintype "power_in"))
      (node (ref "U10") (pin "G7") (pinfunction "VDD_G7") (pintype "power_in"))
      (node (ref "U10") (pin "H2") (pinfunction "VDDQ_H2") (pintype "power_in"))
      (node (ref "U10") (pin "H9") (pinfunction "VDDQ_H9") (pintype "power_in"))
      (node (ref "U10") (pin "K2") (pinfunction "VDD_K2") (pintype "power_in"))
      (node (ref "U10") (pin "K8") (pinfunction "VDD_K8") (pintype "power_in"))
      (node (ref "U10") (pin "N1") (pinfunction "VDD_N1") (pintype "power_in"))
      (node (ref "U10") (pin "N9") (pinfunction "VDD_N9") (pintype "power_in"))
      (node (ref "U10") (pin "R1") (pinfunction "VDD_R1") (pintype "power_in"))
      (node (ref "U10") (pin "R9") (pinfunction "VDD_R9") (pintype "power_in"))
      (node (ref "U11") (pin "A1") (pinfunction "VDDQ_A1") (pintype "power_in"))
      (node (ref "U11") (pin "A8") (pinfunction "VDDQ_A8") (pintype "power_in"))
      (node (ref "U11") (pin "B2") (pinfunction "VDD_B2") (pintype "power_in"))
      (node (ref "U11") (pin "C1") (pinfunction "VDDQ_C1") (pintype "power_in"))
      (node (ref "U11") (pin "C9") (pinfunction "VDDQ_C9") (pintype "power_in"))
      (node (ref "U11") (pin "D2") (pinfunction "VDDQ_D2") (pintype "power_in"))
      (node (ref "U11") (pin "D9") (pinfunction "VDD_D9") (pintype "power_in"))
      (node (ref "U11") (pin "E9") (pinfunction "VDDQ_E9") (pintype "power_in"))
      (node (ref "U11") (pin "F1") (pinfunction "VDDQ_F1") (pintype "power_in"))
      (node (ref "U11") (pin "G7") (pinfunction "VDD_G7") (pintype "power_in"))
      (node (ref "U11") (pin "H2") (pinfunction "VDDQ_H2") (pintype "power_in"))
      (node (ref "U11") (pin "H9") (pinfunction "VDDQ_H9") (pintype "power_in"))
      (node (ref "U11") (pin "K2") (pinfunction "VDD_K2") (pintype "power_in"))
      (node (ref "U11") (pin "K8") (pinfunction "VDD_K8") (pintype "power_in"))
      (node (ref "U11") (pin "N1") (pinfunction "VDD_N1") (pintype "power_in"))
      (node (ref "U11") (pin "N9") (pinfunction "VDD_N9") (pintype "power_in"))
      (node (ref "U11") (pin "R1") (pinfunction "VDD_R1") (pintype "power_in"))
      (node (ref "U11") (pin "R9") (pinfunction "VDD_R9") (pintype "power_in"))
    )
    (net (code "78") (name "DDR_VREF") (class "Default")
      (node (ref "C106") (pin "2") (pinfunction "2_2") (pintype "passive"))
      (node (ref "C107") (pin "2") (pinfunction "2_2") (pintype "passive"))
      (node (ref "R59") (pin "1") (pinfunction "1_1") (pintype "passive"))
      (node (ref "R63") (pin "2") (pinfunction "2_2") (pintype "passive"))
      (node (ref "U10") (pin "H1") (pinfunction "VREFDQ_H1") (pintype "input"))
      (node (ref "U10") (pin "M8") (pinfunction "VREFCA_M8") (pintype "input"))
      (node (ref "U11") (pin "H1") (pinfunction "VREFDQ_H1") (pintype "input"))
      (node (ref "U11") (pin "M8") (pinfunction "VREFCA_M8") (pintype "input"))
      (node (ref "U9") (pin "H6") (pinfunction "PS_DDR_VREF0_502_H6") (pintype "input"))
      (node (ref "U9") (pin "P6") (pinfunction "PS_DDR_VREF1_502_P6") (pintype "input"))
    )
    (net (code "79") (name "GND") (class "Default")
      (node (ref "C105") (pin "1") (pinfunction "1_1") (pintype "passive"))
      (node (ref "C106") (pin "1") (pinfunction "1_1") (pintype "passive"))
      (node (ref "C107") (pin "1") (pinfunction "1_1") (pintype "passive"))
      (node (ref "R52") (pin "1") (pinfunction "1_1") (pintype "passive"))
      (node (ref "R53") (pin "1") (pinfunction "1_1") (pintype "passive"))
      (node (ref "R54") (pin "1") (pinfunction "1_1") (pintype "passive"))
      (node (ref "R58") (pin "2") (pinfunction "2_2") (pintype "passive"))
      (node (ref "R60") (pin "1") (pinfunction "1_1") (pintype "passive"))
      (node (ref "R61") (pin "1") (pinfunction "1_1") (pintype "passive"))
      (node (ref "R62") (pin "1") (pinfunction "1_1") (pintype "passive"))
      (node (ref "R63") (pin "1") (pinfunction "1_1") (pintype "passive"))
      (node (ref "U10") (pin "A9") (pinfunction "VSS_A9") (pintype "power_in"))
      (node (ref "U10") (pin "B1") (pinfunction "VSSQ_B1") (pintype "power_in"))
      (node (ref "U10") (pin "B3") (pinfunction "VSS_B3") (pintype "power_in"))
      (node (ref "U10") (pin "B9") (pinfunction "VSSQ_B9") (pintype "power_in"))
      (node (ref "U10") (pin "D1") (pinfunction "VSSQ_D1") (pintype "power_in"))
      (node (ref "U10") (pin "D8") (pinfunction "VSSQ_D8") (pintype "power_in"))
      (node (ref "U10") (pin "E1") (pinfunction "VSS_E1") (pintype "power_in"))
      (node (ref "U10") (pin "E2") (pinfunction "VSSQ_E2") (pintype "power_in"))
      (node (ref "U10") (pin "E8") (pinfunction "VSSQ_E8") (pintype "power_in"))
      (node (ref "U10") (pin "F9") (pinfunction "VSSQ_F9") (pintype "power_in"))
      (node (ref "U10") (pin "G1") (pinfunction "VSSQ_G1") (pintype "power_in"))
      (node (ref "U10") (pin "G8") (pinfunction "VSS_G8") (pintype "power_in"))
      (node (ref "U10") (pin "G9") (pinfunction "VSSQ_G9") (pintype "power_in"))
      (node (ref "U10") (pin "J2") (pinfunction "VSS_J2") (pintype "power_in"))
      (node (ref "U10") (pin "J8") (pinfunction "VSS_J8") (pintype "power_in"))
      (node (ref "U10") (pin "M1") (pinfunction "VSS_M1") (pintype "power_in"))
      (node (ref "U10") (pin "M9") (pinfunction "VSS_M9") (pintype "power_in"))
      (node (ref "U10") (pin "P1") (pinfunction "VSS_P1") (pintype "power_in"))
      (node (ref "U10") (pin "P9") (pinfunction "VSS_P9") (pintype "power_in"))
      (node (ref "U10") (pin "T1") (pinfunction "VSS_T1") (pintype "power_in"))
      (node (ref "U10") (pin "T9") (pinfunction "VSS_T9") (pintype "power_in"))
      (node (ref "U11") (pin "A9") (pinfunction "VSS_A9") (pintype "power_in"))
      (node (ref "U11") (pin "B1") (pinfunction "VSSQ_B1") (pintype "power_in"))
      (node (ref "U11") (pin "B3") (pinfunction "VSS_B3") (pintype "power_in"))
      (node (ref "U11") (pin "B9") (pinfunction "VSSQ_B9") (pintype "power_in"))
      (node (ref "U11") (pin "D1") (pinfunction "VSSQ_D1") (pintype "power_in"))
      (node (ref "U11") (pin "D8") (pinfunction "VSSQ_D8") (pintype "power_in"))
      (node (ref "U11") (pin "E1") (pinfunction "VSS_E1") (pintype "power_in"))
      (node (ref "U11") (pin "E2") (pinfunction "VSSQ_E2") (pintype "power_in"))
      (node (ref "U11") (pin "E8") (pinfunction "VSSQ_E8") (pintype "power_in"))
      (node (ref "U11") (pin "F9") (pinfunction "VSSQ_F9") (pintype "power_in"))
      (node (ref "U11") (pin "G1") (pinfunction "VSSQ_G1") (pintype "power_in"))
      (node (ref "U11") (pin "G8") (pinfunction "VSS_G8") (pintype "power_in"))
      (node (ref "U11") (pin "G9") (pinfunction "VSSQ_G9") (pintype "power_in"))
      (node (ref "U11") (pin "J2") (pinfunction "VSS_J2") (pintype "power_in"))
      (node (ref "U11") (pin "J8") (pinfunction "VSS_J8") (pintype "power_in"))
      (node (ref "U11") (pin "M1") (pinfunction "VSS_M1") (pintype "power_in"))
      (node (ref "U11") (pin "M9") (pinfunction "VSS_M9") (pintype "power_in"))
      (node (ref "U11") (pin "P1") (pinfunction "VSS_P1") (pintype "power_in"))
      (node (ref "U11") (pin "P9") (pinfunction "VSS_P9") (pintype "power_in"))
      (node (ref "U11") (pin "T1") (pinfunction "VSS_T1") (pintype "power_in"))
      (node (ref "U11") (pin "T9") (pinfunction "VSS_T9") (pintype "power_in"))
    )
    (net (code "80") (name "VTTDDR_PS") (class "Default")
      (node (ref "C105") (pin "2") (pinfunction "2_2") (pintype "passive"))
      (node (ref "R27") (pin "2") (pinfunction "2_2") (pintype "passive"))
      (node (ref "R28") (pin "2") (pinfunction "2_2") (pintype "passive"))
      (node (ref "R29") (pin "2") (pinfunction "2_2") (pintype "passive"))
      (node (ref "R30") (pin "2") (pinfunction "2_2") (pintype "passive"))
      (node (ref "R31") (pin "2") (pinfunction "2_2") (pintype "passive"))
      (node (ref "R32") (pin "2") (pinfunction "2_2") (pintype "passive"))
      (node (ref "R33") (pin "2") (pinfunction "2_2") (pintype "passive"))
      (node (ref "R34") (pin "2") (pinfunction "2_2") (pintype "passive"))
      (node (ref "R35") (pin "2") (pinfunction "2_2") (pintype "passive"))
      (node (ref "R36") (pin "2") (pinfunction "2_2") (pintype "passive"))
      (node (ref "R37") (pin "2") (pinfunction "2_2") (pintype "passive"))
      (node (ref "R38") (pin "2") (pinfunction "2_2") (pintype "passive"))
      (node (ref "R39") (pin "2") (pinfunction "2_2") (pintype "passive"))
      (node (ref "R40") (pin "2") (pinfunction "2_2") (pintype "passive"))
      (node (ref "R41") (pin "2") (pinfunction "2_2") (pintype "passive"))
      (node (ref "R42") (pin "2") (pinfunction "2_2") (pintype "passive"))
      (node (ref "R43") (pin "2") (pinfunction "2_2") (pintype "passive"))
      (node (ref "R44") (pin "2") (pinfunction "2_2") (pintype "passive"))
      (node (ref "R45") (pin "2") (pinfunction "2_2") (pintype "passive"))
      (node (ref "R46") (pin "2") (pinfunction "2_2") (pintype "passive"))
      (node (ref "R47") (pin "2") (pinfunction "2_2") (pintype "passive"))
      (node (ref "R48") (pin "2") (pinfunction "2_2") (pintype "passive"))
      (node (ref "R49") (pin "2") (pinfunction "2_2") (pintype "passive"))
      (node (ref "R50") (pin "2") (pinfunction "2_2") (pintype "passive"))
      (node (ref "R57") (pin "1") (pinfunction "1_1") (pintype "passive"))
      (node (ref "R60") (pin "2") (pinfunction "2_2") (pintype "passive"))
    )
    (net (code "81") (name "unconnected-(U10C-NC-PadJ1)") (class "Default")
      (node (ref "U10") (pin "J1") (pinfunction "NC_J1") (pintype "passive+no_connect"))
    )
    (net (code "82") (name "unconnected-(U10C-NC-PadJ9)") (class "Default")
      (node (ref "U10") (pin "J9") (pinfunction "NC_J9") (pintype "passive+no_connect"))
    )
    (net (code "83") (name "unconnected-(U10C-NC-PadL1)") (class "Default")
      (node (ref "U10") (pin "L1") (pinfunction "NC_L1") (pintype "passive+no_connect"))
    )
    (net (code "84") (name "unconnected-(U10C-NC-PadL9)") (class "Default")
      (node (ref "U10") (pin "L9") (pinfunction "NC_L9") (pintype "passive+no_connect"))
    )
    (net (code "85") (name "unconnected-(U10C-NC-PadM7)") (class "Default")
      (node (ref "U10") (pin "M7") (pinfunction "NC_M7") (pintype "passive+no_connect"))
    )
    (net (code "86") (name "unconnected-(U11C-NC-PadJ1)") (class "Default")
      (node (ref "U11") (pin "J1") (pinfunction "NC_J1") (pintype "passive+no_connect"))
    )
    (net (code "87") (name "unconnected-(U11C-NC-PadJ9)") (class "Default")
      (node (ref "U11") (pin "J9") (pinfunction "NC_J9") (pintype "passive+no_connect"))
    )
    (net (code "88") (name "unconnected-(U11C-NC-PadL1)") (class "Default")
      (node (ref "U11") (pin "L1") (pinfunction "NC_L1") (pintype "passive+no_connect"))
    )
    (net (code "89") (name "unconnected-(U11C-NC-PadL9)") (class "Default")
      (node (ref "U11") (pin "L9") (pinfunction "NC_L9") (pintype "passive+no_connect"))
    )
    (net (code "90") (name "unconnected-(U11C-NC-PadM7)") (class "Default")
      (node (ref "U11") (pin "M7") (pinfunction "NC_M7") (pintype "passive+no_connect"))
    )
  )
)
